# Gaga_Soundsystem_new.net
KiCad netlist of a schematic drawn in EAGLE
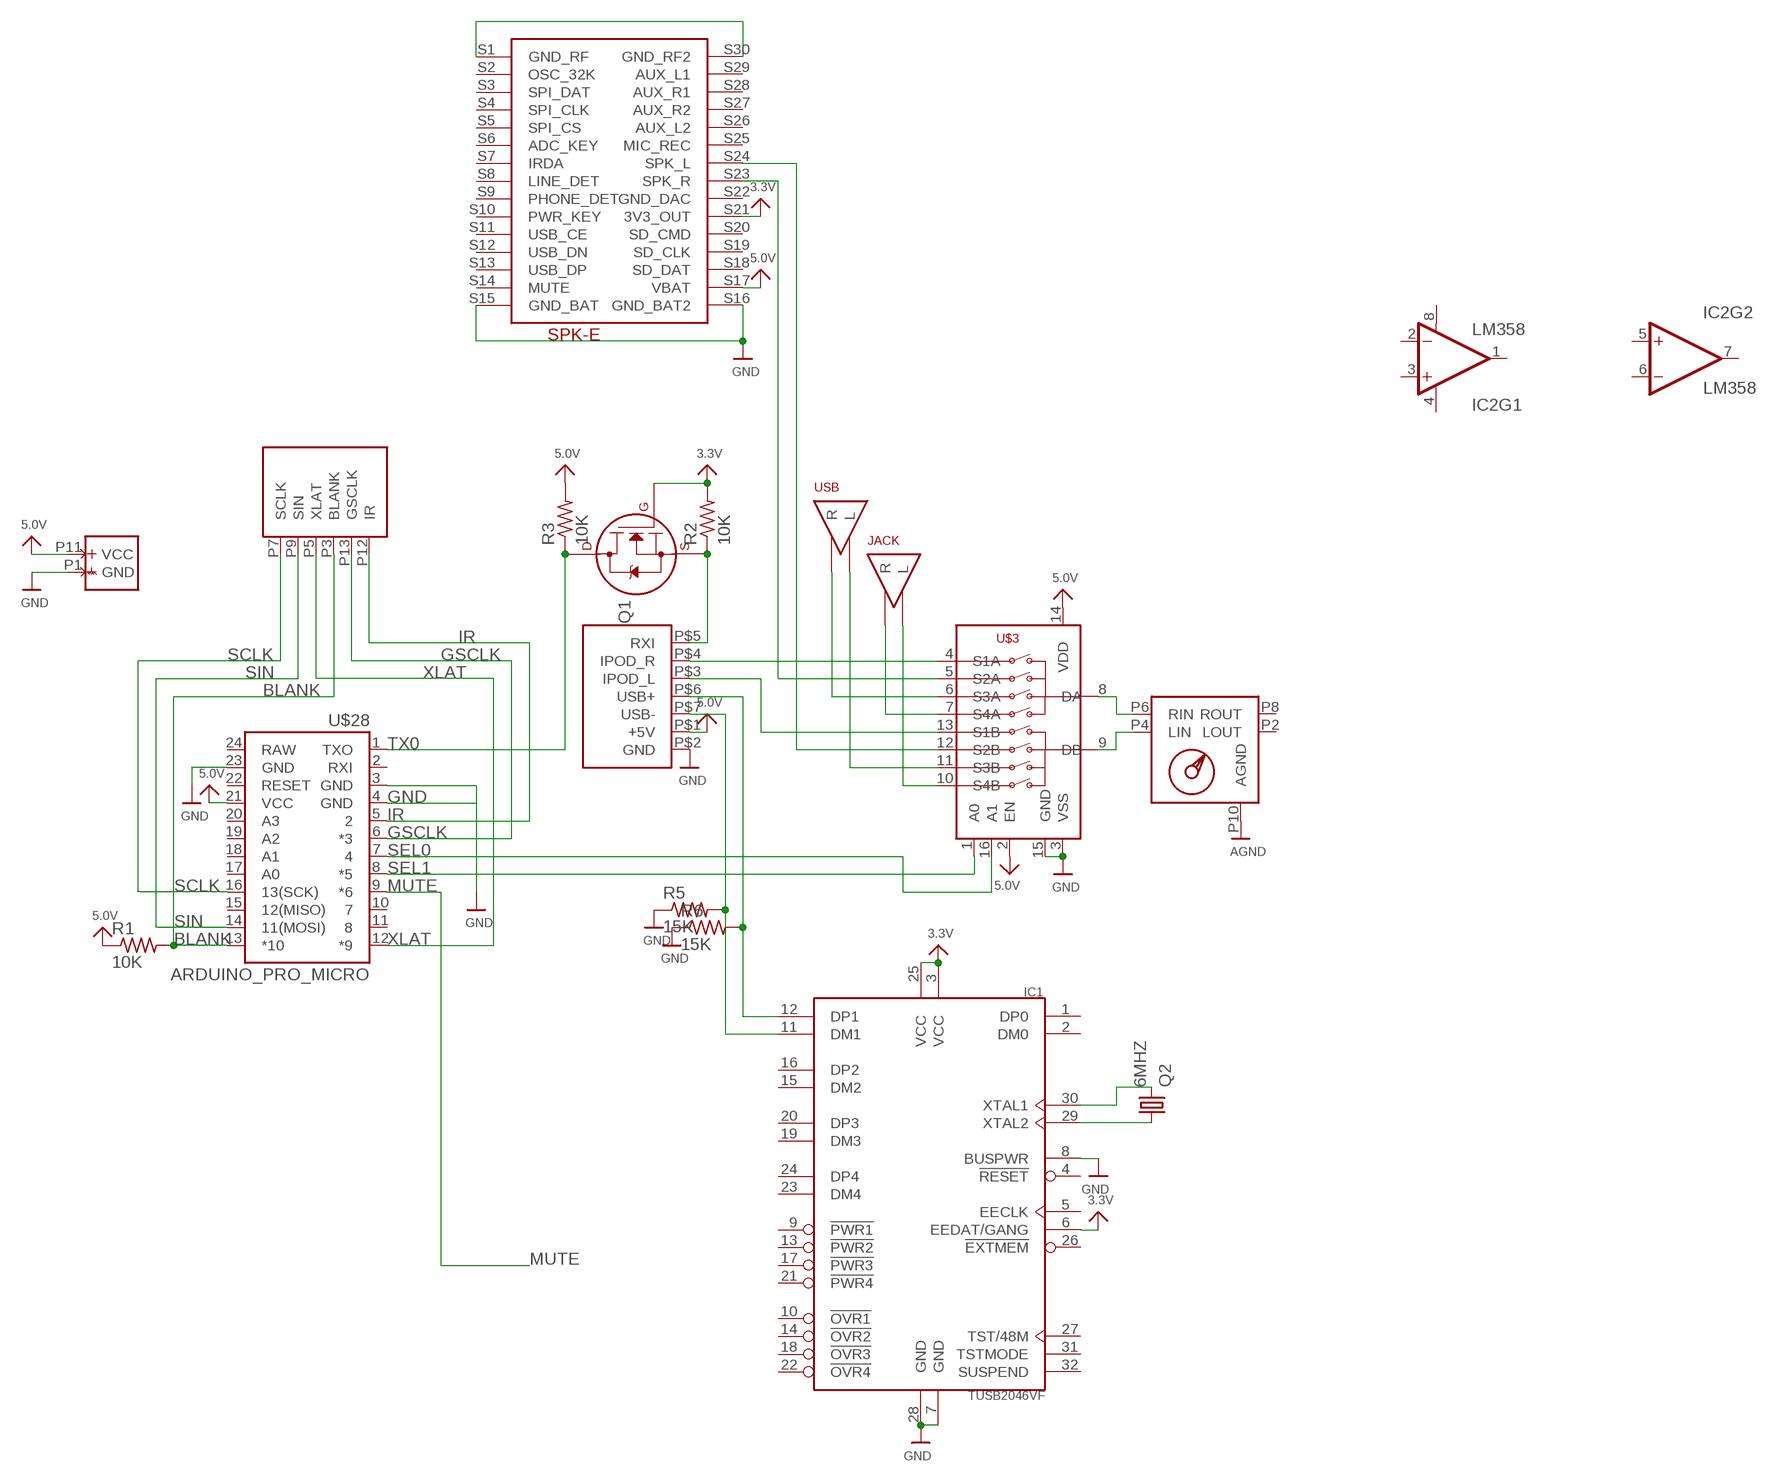
[diagram p0: schematic, sheet 1]

(export (version "E")
  (design (tool "Eeschema 10.0.6"))
  (components
    (comp (ref "IC1")
      (value "TUSB2046VF")
      (footprint "eagle-import:TQFP32-08")
      (libsource (lib "eagle-import") (part "TUSB2046VF"))
    )
    (comp (ref "IC2")
      (value "LM358")
      (footprint "eagle-import:DIP08")
      (libsource (lib "eagle-import") (part "LM358"))
    )
    (comp (ref "JACK")
      (value "JACK")
      (footprint "eagle-import:AUDIOCON")
      (libsource (lib "eagle-import") (part "AUDIOCON"))
    )
    (comp (ref "Q1")
      (value "2N7000_TO92")
      (footprint "eagle-import:TO-92")
      (libsource (lib "eagle-import") (part "2N700_TO920"))
    )
    (comp (ref "Q2")
      (value "6MHZ")
      (footprint "eagle-import:HC49_S")
      (libsource (lib "eagle-import") (part "CRYSTALHC49S"))
    )
    (comp (ref "R1")
      (value "10K")
      (footprint "eagle-import:0207_7")
      (libsource (lib "eagle-import") (part "R-US_0207/7"))
    )
    (comp (ref "R2")
      (value "10K")
      (footprint "eagle-import:M0805")
      (libsource (lib "eagle-import") (part "R-US_M0805"))
    )
    (comp (ref "R3")
      (value "10K")
      (footprint "eagle-import:R0805")
      (libsource (lib "eagle-import") (part "R-US_R0805"))
    )
    (comp (ref "R5")
      (value "15K")
      (footprint "eagle-import:R0805")
      (libsource (lib "eagle-import") (part "R-US_R0805"))
    )
    (comp (ref "R6")
      (value "15K")
      (footprint "eagle-import:R0805")
      (libsource (lib "eagle-import") (part "R-US_R0805"))
    )
    (comp (ref "U$1")
      (value "OTHERSIDE")
      (footprint "eagle-import:OTHERSIDE")
      (libsource (lib "eagle-import") (part "OTHERSIDE"))
    )
    (comp (ref "U$3")
      (value "ADG709")
      (footprint "eagle-import:TSSOP16")
      (libsource (lib "eagle-import") (part "ADG709"))
    )
    (comp (ref "U$5")
      (value "IPODCON")
      (footprint "eagle-import:IPODCON")
      (libsource (lib "eagle-import") (part "IPODCON"))
    )
    (comp (ref "U$7")
      (value "SPK-E")
      (footprint "eagle-import:SPK-E")
      (libsource (lib "eagle-import") (part "SPK-E"))
    )
    (comp (ref "U$28")
      (value "ARDUINO_PRO_MICRO")
      (footprint "eagle-import:ARDUINO_PRO_MICRO")
      (libsource (lib "eagle-import") (part "ARDUINO_PRO_MICRO"))
    )
    (comp (ref "USB")
      (value "USB")
      (footprint "eagle-import:AUDIOCON")
      (libsource (lib "eagle-import") (part "AUDIOCON"))
    )
  )
  (nets
    (net (code "1") (name "/BLANK") (class "Default")
      (node (ref "R1") (pin "2") (pinfunction "2_2") (pintype "passive"))
      (node (ref "U$1") (pin "P3") (pinfunction "BLANK_P3") (pintype "bidirectional"))
      (node (ref "U$28") (pin "13") (pinfunction "*10_13") (pintype "bidirectional"))
    )
    (net (code "2") (name "/GSCLK") (class "Default")
      (node (ref "U$1") (pin "P13") (pinfunction "GSCLK_P13") (pintype "bidirectional"))
      (node (ref "U$28") (pin "6") (pinfunction "*3_6") (pintype "bidirectional"))
    )
    (net (code "3") (name "/IR") (class "Default")
      (node (ref "U$1") (pin "P12") (pinfunction "IR_P12") (pintype "bidirectional"))
      (node (ref "U$28") (pin "5") (pinfunction "2_5") (pintype "bidirectional"))
    )
    (net (code "4") (name "/MUTE") (class "Default")
      (node (ref "U$28") (pin "9") (pinfunction "*6_9") (pintype "bidirectional"))
    )
    (net (code "5") (name "/SCLK") (class "Default")
      (node (ref "U$1") (pin "P7") (pinfunction "SCLK_P7") (pintype "bidirectional"))
      (node (ref "U$28") (pin "16") (pinfunction "13(SCK)_16") (pintype "bidirectional"))
    )
    (net (code "6") (name "/SEL0") (class "Default")
      (node (ref "U$28") (pin "7") (pinfunction "4_7") (pintype "bidirectional"))
      (node (ref "U$3") (pin "16") (pinfunction "A1_16") (pintype "bidirectional"))
    )
    (net (code "7") (name "/SEL1") (class "Default")
      (node (ref "U$28") (pin "8") (pinfunction "*5_8") (pintype "bidirectional"))
      (node (ref "U$3") (pin "1") (pinfunction "A0_1") (pintype "bidirectional"))
    )
    (net (code "8") (name "/SIN") (class "Default")
      (node (ref "U$1") (pin "P9") (pinfunction "SIN_P9") (pintype "bidirectional"))
      (node (ref "U$28") (pin "14") (pinfunction "11(MOSI)_14") (pintype "bidirectional"))
    )
    (net (code "9") (name "/TX0") (class "Default")
      (node (ref "Q1") (pin "3") (pinfunction "D_3") (pintype "bidirectional"))
      (node (ref "R3") (pin "1") (pinfunction "1_1") (pintype "passive"))
      (node (ref "U$28") (pin "1") (pinfunction "TXO_1") (pintype "bidirectional"))
    )
    (net (code "10") (name "/V+") (class "Default")
      (node (ref "IC2") (pin "8") (pinfunction "V+_8") (pintype "power_in"))
    )
    (net (code "11") (name "/V-") (class "Default")
      (node (ref "IC2") (pin "4") (pinfunction "V-_4") (pintype "power_in"))
    )
    (net (code "12") (name "/XLAT") (class "Default")
      (node (ref "U$1") (pin "P5") (pinfunction "XLAT_P5") (pintype "bidirectional"))
      (node (ref "U$28") (pin "12") (pinfunction "*9_12") (pintype "bidirectional"))
    )
    (net (code "13") (name "3.3V") (class "Default")
      (node (ref "IC1") (pin "25") (pinfunction "VCC_25") (pintype "power_in"))
      (node (ref "IC1") (pin "3") (pinfunction "VCC_3") (pintype "power_in"))
      (node (ref "IC1") (pin "6") (pinfunction "EEDAT/GANG_6") (pintype "bidirectional"))
      (node (ref "Q1") (pin "2") (pinfunction "G_2") (pintype "tri_state"))
      (node (ref "R2") (pin "2") (pinfunction "2_2") (pintype "passive"))
      (node (ref "U$7") (pin "S21") (pinfunction "3V3_OUT_S21") (pintype "bidirectional"))
    )
    (net (code "14") (name "5.0V") (class "Default")
      (node (ref "R1") (pin "1") (pinfunction "1_1") (pintype "passive"))
      (node (ref "R3") (pin "2") (pinfunction "2_2") (pintype "passive"))
      (node (ref "U$1") (pin "P11") (pinfunction "VCC_P11") (pintype "bidirectional"))
      (node (ref "U$28") (pin "21") (pinfunction "VCC_21") (pintype "bidirectional"))
      (node (ref "U$3") (pin "14") (pinfunction "VDD_14") (pintype "bidirectional"))
      (node (ref "U$3") (pin "2") (pinfunction "EN_2") (pintype "bidirectional"))
      (node (ref "U$5") (pin "P$1") (pinfunction "+5V_P$1") (pintype "bidirectional"))
      (node (ref "U$7") (pin "S17") (pinfunction "VBAT_S17") (pintype "bidirectional"))
    )
    (net (code "15") (name "AGND") (class "Default")
      (node (ref "U$1") (pin "P10") (pinfunction "AGND_P10") (pintype "bidirectional"))
    )
    (net (code "16") (name "GND") (class "Default")
      (node (ref "IC1") (pin "28") (pinfunction "GND_28") (pintype "power_in"))
      (node (ref "IC1") (pin "7") (pinfunction "GND_7") (pintype "power_in"))
      (node (ref "IC1") (pin "8") (pinfunction "BUSPWR_8") (pintype "input"))
      (node (ref "R5") (pin "1") (pinfunction "1_1") (pintype "passive"))
      (node (ref "R6") (pin "1") (pinfunction "1_1") (pintype "passive"))
      (node (ref "U$1") (pin "P1") (pinfunction "GND_P1") (pintype "bidirectional"))
      (node (ref "U$28") (pin "23") (pinfunction "GND_23") (pintype "bidirectional"))
      (node (ref "U$28") (pin "3") (pinfunction "GND_3") (pintype "bidirectional"))
      (node (ref "U$28") (pin "4") (pinfunction "GND_4") (pintype "bidirectional"))
      (node (ref "U$3") (pin "15") (pinfunction "GND_15") (pintype "bidirectional"))
      (node (ref "U$3") (pin "3") (pinfunction "VSS_3") (pintype "bidirectional"))
      (node (ref "U$5") (pin "P$2") (pinfunction "GND_P$2") (pintype "bidirectional"))
      (node (ref "U$7") (pin "S15") (pinfunction "GND_BAT_S15") (pintype "bidirectional"))
      (node (ref "U$7") (pin "S16") (pinfunction "GND_BAT2_S16") (pintype "bidirectional"))
    )
    (net (code "17") (name "Net-(IC1-DM1)") (class "Default")
      (node (ref "IC1") (pin "11") (pinfunction "DM1_11") (pintype "bidirectional"))
      (node (ref "R5") (pin "2") (pinfunction "2_2") (pintype "passive"))
      (node (ref "U$5") (pin "P$7") (pinfunction "USB-_P$7") (pintype "bidirectional"))
    )
    (net (code "18") (name "Net-(IC1-DP1)") (class "Default")
      (node (ref "IC1") (pin "12") (pinfunction "DP1_12") (pintype "bidirectional"))
      (node (ref "R6") (pin "2") (pinfunction "2_2") (pintype "passive"))
      (node (ref "U$5") (pin "P$6") (pinfunction "USB+_P$6") (pintype "bidirectional"))
    )
    (net (code "19") (name "Net-(IC1-XTAL1)") (class "Default")
      (node (ref "IC1") (pin "30") (pinfunction "XTAL1_30") (pintype "bidirectional"))
      (node (ref "Q2") (pin "2") (pinfunction "2_2") (pintype "passive"))
    )
    (net (code "20") (name "Net-(IC1-XTAL2)") (class "Default")
      (node (ref "IC1") (pin "29") (pinfunction "XTAL2_29") (pintype "bidirectional"))
      (node (ref "Q2") (pin "1") (pinfunction "1_1") (pintype "passive"))
    )
    (net (code "21") (name "Net-(JACK-L)") (class "Default")
      (node (ref "JACK") (pin "P$2") (pinfunction "L_P$2") (pintype "bidirectional"))
      (node (ref "U$3") (pin "10") (pinfunction "S4B_10") (pintype "bidirectional"))
    )
    (net (code "22") (name "Net-(JACK-R)") (class "Default")
      (node (ref "JACK") (pin "P$1") (pinfunction "R_P$1") (pintype "bidirectional"))
      (node (ref "U$3") (pin "7") (pinfunction "S4A_7") (pintype "bidirectional"))
    )
    (net (code "23") (name "Net-(Q1-S)") (class "Default")
      (node (ref "Q1") (pin "1") (pinfunction "S_1") (pintype "bidirectional"))
      (node (ref "R2") (pin "1") (pinfunction "1_1") (pintype "passive"))
      (node (ref "U$5") (pin "P$5") (pinfunction "RXI_P$5") (pintype "bidirectional"))
    )
    (net (code "24") (name "Net-(U$1B-LIN)") (class "Default")
      (node (ref "U$1") (pin "P4") (pinfunction "LIN_P4") (pintype "bidirectional"))
      (node (ref "U$3") (pin "9") (pinfunction "DB_9") (pintype "bidirectional"))
    )
    (net (code "25") (name "Net-(U$1B-RIN)") (class "Default")
      (node (ref "U$1") (pin "P6") (pinfunction "RIN_P6") (pintype "bidirectional"))
      (node (ref "U$3") (pin "8") (pinfunction "DA_8") (pintype "bidirectional"))
    )
    (net (code "26") (name "Net-(U$3-S1A)") (class "Default")
      (node (ref "U$3") (pin "4") (pinfunction "S1A_4") (pintype "bidirectional"))
      (node (ref "U$5") (pin "P$4") (pinfunction "IPOD_R_P$4") (pintype "bidirectional"))
    )
    (net (code "27") (name "Net-(U$3-S1B)") (class "Default")
      (node (ref "U$3") (pin "13") (pinfunction "S1B_13") (pintype "bidirectional"))
      (node (ref "U$5") (pin "P$3") (pinfunction "IPOD_L_P$3") (pintype "bidirectional"))
    )
    (net (code "28") (name "Net-(U$3-S2A)") (class "Default")
      (node (ref "U$3") (pin "5") (pinfunction "S2A_5") (pintype "bidirectional"))
      (node (ref "U$7") (pin "S23") (pinfunction "SPK_R_S23") (pintype "bidirectional"))
    )
    (net (code "29") (name "Net-(U$3-S2B)") (class "Default")
      (node (ref "U$3") (pin "12") (pinfunction "S2B_12") (pintype "bidirectional"))
      (node (ref "U$7") (pin "S24") (pinfunction "SPK_L_S24") (pintype "bidirectional"))
    )
    (net (code "30") (name "Net-(U$3-S3A)") (class "Default")
      (node (ref "U$3") (pin "6") (pinfunction "S3A_6") (pintype "bidirectional"))
      (node (ref "USB") (pin "P$1") (pinfunction "R_P$1") (pintype "bidirectional"))
    )
    (net (code "31") (name "Net-(U$3-S3B)") (class "Default")
      (node (ref "U$3") (pin "11") (pinfunction "S3B_11") (pintype "bidirectional"))
      (node (ref "USB") (pin "P$2") (pinfunction "L_P$2") (pintype "bidirectional"))
    )
    (net (code "32") (name "Net-(U$7-GND_RF)") (class "Default")
      (node (ref "U$7") (pin "S1") (pinfunction "GND_RF_S1") (pintype "bidirectional"))
      (node (ref "U$7") (pin "S30") (pinfunction "GND_RF2_S30") (pintype "bidirectional"))
    )
    (net (code "33") (name "unconnected-(IC1-DM0-Pad2)") (class "Default")
      (node (ref "IC1") (pin "2") (pinfunction "DM0_2") (pintype "bidirectional"))
    )
    (net (code "34") (name "unconnected-(IC1-DM2-Pad15)") (class "Default")
      (node (ref "IC1") (pin "15") (pinfunction "DM2_15") (pintype "bidirectional"))
    )
    (net (code "35") (name "unconnected-(IC1-DM3-Pad19)") (class "Default")
      (node (ref "IC1") (pin "19") (pinfunction "DM3_19") (pintype "bidirectional"))
    )
    (net (code "36") (name "unconnected-(IC1-DM4-Pad23)") (class "Default")
      (node (ref "IC1") (pin "23") (pinfunction "DM4_23") (pintype "bidirectional"))
    )
    (net (code "37") (name "unconnected-(IC1-DP0-Pad1)") (class "Default")
      (node (ref "IC1") (pin "1") (pinfunction "DP0_1") (pintype "bidirectional"))
    )
    (net (code "38") (name "unconnected-(IC1-DP2-Pad16)") (class "Default")
      (node (ref "IC1") (pin "16") (pinfunction "DP2_16") (pintype "bidirectional"))
    )
    (net (code "39") (name "unconnected-(IC1-DP3-Pad20)") (class "Default")
      (node (ref "IC1") (pin "20") (pinfunction "DP3_20") (pintype "bidirectional"))
    )
    (net (code "40") (name "unconnected-(IC1-DP4-Pad24)") (class "Default")
      (node (ref "IC1") (pin "24") (pinfunction "DP4_24") (pintype "bidirectional"))
    )
    (net (code "41") (name "unconnected-(IC1-EECLK-Pad5)") (class "Default")
      (node (ref "IC1") (pin "5") (pinfunction "EECLK_5") (pintype "bidirectional"))
    )
    (net (code "42") (name "unconnected-(IC1-SUSPEND-Pad32)") (class "Default")
      (node (ref "IC1") (pin "32") (pinfunction "SUSPEND_32") (pintype "output"))
    )
    (net (code "43") (name "unconnected-(IC1-TSTMODE-Pad31)") (class "Default")
      (node (ref "IC1") (pin "31") (pinfunction "TSTMODE_31") (pintype "input"))
    )
    (net (code "44") (name "unconnected-(IC1-TST{slash}48M-Pad27)") (class "Default")
      (node (ref "IC1") (pin "27") (pinfunction "TST/48M_27") (pintype "bidirectional"))
    )
    (net (code "45") (name "unconnected-(IC1-~{EXTMEM}-Pad26)") (class "Default")
      (node (ref "IC1") (pin "26") (pinfunction "~{EXTMEM}_26") (pintype "bidirectional"))
    )
    (net (code "46") (name "unconnected-(IC1-~{OVR1}-Pad10)") (class "Default")
      (node (ref "IC1") (pin "10") (pinfunction "~{OVR1}_10") (pintype "input"))
    )
    (net (code "47") (name "unconnected-(IC1-~{OVR2}-Pad14)") (class "Default")
      (node (ref "IC1") (pin "14") (pinfunction "~{OVR2}_14") (pintype "input"))
    )
    (net (code "48") (name "unconnected-(IC1-~{OVR3}-Pad18)") (class "Default")
      (node (ref "IC1") (pin "18") (pinfunction "~{OVR3}_18") (pintype "input"))
    )
    (net (code "49") (name "unconnected-(IC1-~{OVR4}-Pad22)") (class "Default")
      (node (ref "IC1") (pin "22") (pinfunction "~{OVR4}_22") (pintype "input"))
    )
    (net (code "50") (name "unconnected-(IC1-~{PWR1}-Pad9)") (class "Default")
      (node (ref "IC1") (pin "9") (pinfunction "~{PWR1}_9") (pintype "output"))
    )
    (net (code "51") (name "unconnected-(IC1-~{PWR2}-Pad13)") (class "Default")
      (node (ref "IC1") (pin "13") (pinfunction "~{PWR2}_13") (pintype "output"))
    )
    (net (code "52") (name "unconnected-(IC1-~{PWR3}-Pad17)") (class "Default")
      (node (ref "IC1") (pin "17") (pinfunction "~{PWR3}_17") (pintype "output"))
    )
    (net (code "53") (name "unconnected-(IC1-~{PWR4}-Pad21)") (class "Default")
      (node (ref "IC1") (pin "21") (pinfunction "~{PWR4}_21") (pintype "output"))
    )
    (net (code "54") (name "unconnected-(IC1-~{RESET}-Pad4)") (class "Default")
      (node (ref "IC1") (pin "4") (pinfunction "~{RESET}_4") (pintype "input"))
    )
    (net (code "55") (name "unconnected-(IC2A-+IN-Pad3)") (class "Default")
      (node (ref "IC2") (pin "3") (pinfunction "+IN_3") (pintype "input"))
    )
    (net (code "56") (name "unconnected-(IC2A--IN-Pad2)") (class "Default")
      (node (ref "IC2") (pin "2") (pinfunction "-IN_2") (pintype "input"))
    )
    (net (code "57") (name "unconnected-(IC2A-OUT-Pad1)") (class "Default")
      (node (ref "IC2") (pin "1") (pinfunction "OUT_1") (pintype "output"))
    )
    (net (code "58") (name "unconnected-(IC2B-+IN-Pad5)") (class "Default")
      (node (ref "IC2") (pin "5") (pinfunction "+IN_5") (pintype "input"))
    )
    (net (code "59") (name "unconnected-(IC2B--IN-Pad6)") (class "Default")
      (node (ref "IC2") (pin "6") (pinfunction "-IN_6") (pintype "input"))
    )
    (net (code "60") (name "unconnected-(IC2B-OUT-Pad7)") (class "Default")
      (node (ref "IC2") (pin "7") (pinfunction "OUT_7") (pintype "output"))
    )
    (net (code "61") (name "unconnected-(U$1B-LOUT-PadP2)") (class "Default")
      (node (ref "U$1") (pin "P2") (pinfunction "LOUT_P2") (pintype "bidirectional"))
    )
    (net (code "62") (name "unconnected-(U$1B-ROUT-PadP8)") (class "Default")
      (node (ref "U$1") (pin "P8") (pinfunction "ROUT_P8") (pintype "bidirectional"))
    )
    (net (code "63") (name "unconnected-(U$7-ADC_KEY-PadS6)") (class "Default")
      (node (ref "U$7") (pin "S6") (pinfunction "ADC_KEY_S6") (pintype "bidirectional"))
    )
    (net (code "64") (name "unconnected-(U$7-AUX_L1-PadS29)") (class "Default")
      (node (ref "U$7") (pin "S29") (pinfunction "AUX_L1_S29") (pintype "bidirectional"))
    )
    (net (code "65") (name "unconnected-(U$7-AUX_L2-PadS26)") (class "Default")
      (node (ref "U$7") (pin "S26") (pinfunction "AUX_L2_S26") (pintype "bidirectional"))
    )
    (net (code "66") (name "unconnected-(U$7-AUX_R1-PadS28)") (class "Default")
      (node (ref "U$7") (pin "S28") (pinfunction "AUX_R1_S28") (pintype "bidirectional"))
    )
    (net (code "67") (name "unconnected-(U$7-AUX_R2-PadS27)") (class "Default")
      (node (ref "U$7") (pin "S27") (pinfunction "AUX_R2_S27") (pintype "bidirectional"))
    )
    (net (code "68") (name "unconnected-(U$7-GND_DAC-PadS22)") (class "Default")
      (node (ref "U$7") (pin "S22") (pinfunction "GND_DAC_S22") (pintype "bidirectional"))
    )
    (net (code "69") (name "unconnected-(U$7-IRDA-PadS7)") (class "Default")
      (node (ref "U$7") (pin "S7") (pinfunction "IRDA_S7") (pintype "bidirectional"))
    )
    (net (code "70") (name "unconnected-(U$7-LINE_DET-PadS8)") (class "Default")
      (node (ref "U$7") (pin "S8") (pinfunction "LINE_DET_S8") (pintype "bidirectional"))
    )
    (net (code "71") (name "unconnected-(U$7-MIC_REC-PadS25)") (class "Default")
      (node (ref "U$7") (pin "S25") (pinfunction "MIC_REC_S25") (pintype "bidirectional"))
    )
    (net (code "72") (name "unconnected-(U$7-MUTE-PadS14)") (class "Default")
      (node (ref "U$7") (pin "S14") (pinfunction "MUTE_S14") (pintype "bidirectional"))
    )
    (net (code "73") (name "unconnected-(U$7-OSC_32K-PadS2)") (class "Default")
      (node (ref "U$7") (pin "S2") (pinfunction "OSC_32K_S2") (pintype "bidirectional"))
    )
    (net (code "74") (name "unconnected-(U$7-PHONE_DET-PadS9)") (class "Default")
      (node (ref "U$7") (pin "S9") (pinfunction "PHONE_DET_S9") (pintype "bidirectional"))
    )
    (net (code "75") (name "unconnected-(U$7-PWR_KEY-PadS10)") (class "Default")
      (node (ref "U$7") (pin "S10") (pinfunction "PWR_KEY_S10") (pintype "bidirectional"))
    )
    (net (code "76") (name "unconnected-(U$7-SD_CLK-PadS19)") (class "Default")
      (node (ref "U$7") (pin "S19") (pinfunction "SD_CLK_S19") (pintype "bidirectional"))
    )
    (net (code "77") (name "unconnected-(U$7-SD_CMD-PadS20)") (class "Default")
      (node (ref "U$7") (pin "S20") (pinfunction "SD_CMD_S20") (pintype "bidirectional"))
    )
    (net (code "78") (name "unconnected-(U$7-SD_DAT-PadS18)") (class "Default")
      (node (ref "U$7") (pin "S18") (pinfunction "SD_DAT_S18") (pintype "bidirectional"))
    )
    (net (code "79") (name "unconnected-(U$7-SPI_CLK-PadS4)") (class "Default")
      (node (ref "U$7") (pin "S4") (pinfunction "SPI_CLK_S4") (pintype "bidirectional"))
    )
    (net (code "80") (name "unconnected-(U$7-SPI_CS-PadS5)") (class "Default")
      (node (ref "U$7") (pin "S5") (pinfunction "SPI_CS_S5") (pintype "bidirectional"))
    )
    (net (code "81") (name "unconnected-(U$7-SPI_DAT-PadS3)") (class "Default")
      (node (ref "U$7") (pin "S3") (pinfunction "SPI_DAT_S3") (pintype "bidirectional"))
    )
    (net (code "82") (name "unconnected-(U$7-USB_CE-PadS11)") (class "Default")
      (node (ref "U$7") (pin "S11") (pinfunction "USB_CE_S11") (pintype "bidirectional"))
    )
    (net (code "83") (name "unconnected-(U$7-USB_DN-PadS12)") (class "Default")
      (node (ref "U$7") (pin "S12") (pinfunction "USB_DN_S12") (pintype "bidirectional"))
    )
    (net (code "84") (name "unconnected-(U$7-USB_DP-PadS13)") (class "Default")
      (node (ref "U$7") (pin "S13") (pinfunction "USB_DP_S13") (pintype "bidirectional"))
    )
    (net (code "85") (name "unconnected-(U$28-7-Pad10)") (class "Default")
      (node (ref "U$28") (pin "10") (pinfunction "7_10") (pintype "bidirectional"))
    )
    (net (code "86") (name "unconnected-(U$28-8-Pad11)") (class "Default")
      (node (ref "U$28") (pin "11") (pinfunction "8_11") (pintype "bidirectional"))
    )
    (net (code "87") (name "unconnected-(U$28-12(MISO)-Pad15)") (class "Default")
      (node (ref "U$28") (pin "15") (pinfunction "12(MISO)_15") (pintype "bidirectional"))
    )
    (net (code "88") (name "unconnected-(U$28-A0-Pad17)") (class "Default")
      (node (ref "U$28") (pin "17") (pinfunction "A0_17") (pintype "bidirectional"))
    )
    (net (code "89") (name "unconnected-(U$28-A1-Pad18)") (class "Default")
      (node (ref "U$28") (pin "18") (pinfunction "A1_18") (pintype "bidirectional"))
    )
    (net (code "90") (name "unconnected-(U$28-A2-Pad19)") (class "Default")
      (node (ref "U$28") (pin "19") (pinfunction "A2_19") (pintype "bidirectional"))
    )
    (net (code "91") (name "unconnected-(U$28-A3-Pad20)") (class "Default")
      (node (ref "U$28") (pin "20") (pinfunction "A3_20") (pintype "bidirectional"))
    )
    (net (code "92") (name "unconnected-(U$28-RAW-Pad24)") (class "Default")
      (node (ref "U$28") (pin "24") (pinfunction "RAW_24") (pintype "bidirectional"))
    )
    (net (code "93") (name "unconnected-(U$28-RESET-Pad22)") (class "Default")
      (node (ref "U$28") (pin "22") (pinfunction "RESET_22") (pintype "bidirectional"))
    )
    (net (code "94") (name "unconnected-(U$28-RXI-Pad2)") (class "Default")
      (node (ref "U$28") (pin "2") (pinfunction "RXI_2") (pintype "bidirectional"))
    )
  )
)
